# crystal-oscillators.net
KiCad netlist of a schematic drawn in EAGLE
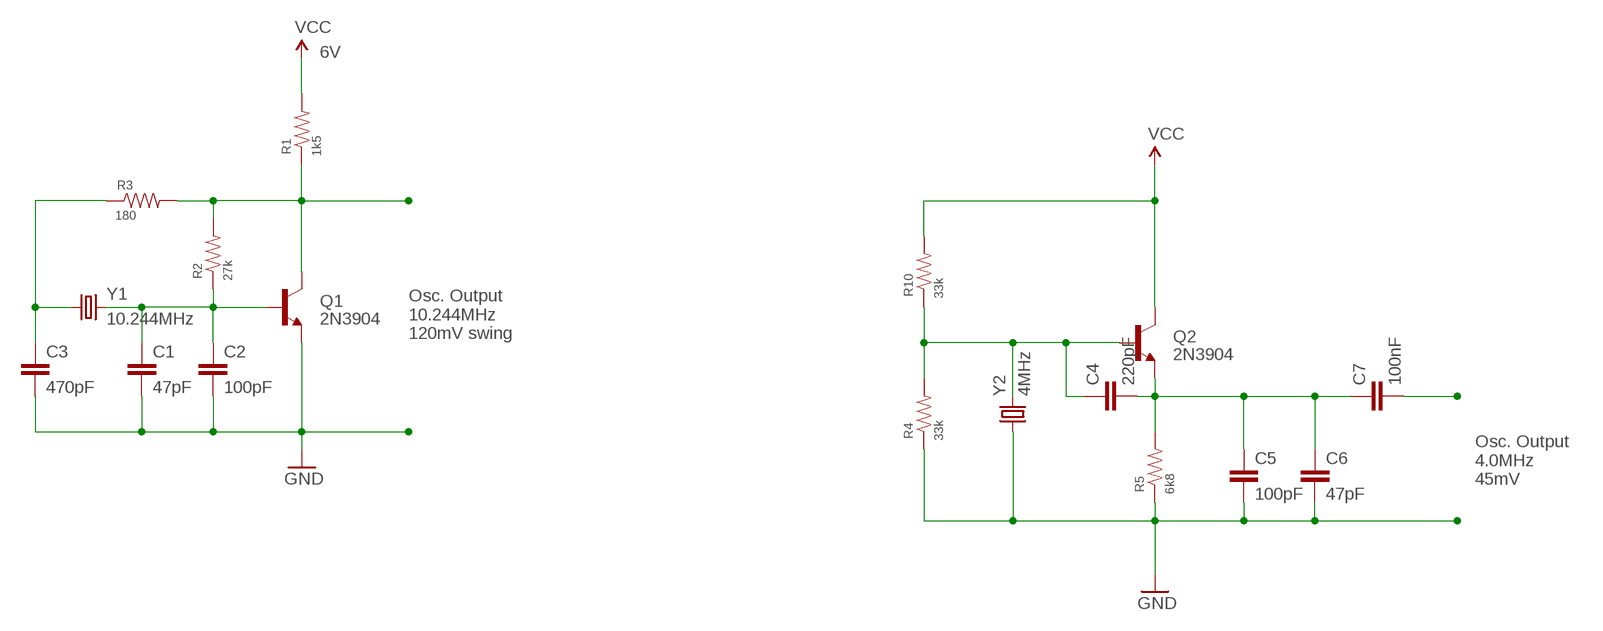
[diagram p0: schematic, sheet 1]

(export (version "E")
  (design (tool "Eeschema 10.0.6"))
  (components
    (comp (ref "C1")
      (value "47pF")
      (footprint "eagle-import:CAP-PTH-SMALL")
      (libsource (lib "eagle-import") (part "CAPPTH"))
    )
    (comp (ref "C2")
      (value "100pF")
      (footprint "eagle-import:CAP-PTH-SMALL")
      (libsource (lib "eagle-import") (part "CAPPTH"))
    )
    (comp (ref "C3")
      (value "470pF")
      (footprint "eagle-import:CAP-PTH-SMALL")
      (libsource (lib "eagle-import") (part "CAPPTH"))
    )
    (comp (ref "C4")
      (value "220pF")
      (footprint "eagle-import:CAP-PTH-SMALL")
      (libsource (lib "eagle-import") (part "CAPPTH"))
    )
    (comp (ref "C5")
      (value "100pF")
      (footprint "eagle-import:CAP-PTH-SMALL")
      (libsource (lib "eagle-import") (part "CAPPTH"))
    )
    (comp (ref "C6")
      (value "47pF")
      (footprint "eagle-import:CAP-PTH-SMALL")
      (libsource (lib "eagle-import") (part "CAPPTH"))
    )
    (comp (ref "C7")
      (value "100nF")
      (footprint "eagle-import:CAP-PTH-SMALL")
      (libsource (lib "eagle-import") (part "CAPPTH"))
    )
    (comp (ref "Q1")
      (value "2N3904")
      (footprint "eagle-import:TO-92")
      (libsource (lib "eagle-import") (part "TRANSISTOR_NPNP2N2222A"))
    )
    (comp (ref "Q2")
      (value "2N3904")
      (footprint "eagle-import:TO-92")
      (libsource (lib "eagle-import") (part "TRANSISTOR_NPNP2N2222A"))
    )
    (comp (ref "R1")
      (value "1k5")
      (footprint "eagle-import:VERT-PTH")
      (libsource (lib "eagle-import") (part "RESISTOR-PTH"))
    )
    (comp (ref "R2")
      (value "27k")
      (footprint "eagle-import:VERT-PTH")
      (libsource (lib "eagle-import") (part "RESISTOR-PTH"))
    )
    (comp (ref "R3")
      (value "180")
      (footprint "eagle-import:VERT-PTH")
      (libsource (lib "eagle-import") (part "RESISTOR-PTH"))
    )
    (comp (ref "R4")
      (value "33k")
      (footprint "eagle-import:VERT-PTH")
      (libsource (lib "eagle-import") (part "RESISTOR-PTH"))
    )
    (comp (ref "R5")
      (value "6k8")
      (footprint "eagle-import:VERT-PTH")
      (libsource (lib "eagle-import") (part "RESISTOR-PTH"))
    )
    (comp (ref "R10")
      (value "33k")
      (footprint "eagle-import:VERT-PTH")
      (libsource (lib "eagle-import") (part "RESISTOR-PTH"))
    )
    (comp (ref "Y1")
      (value "10.244MHz")
      (footprint "eagle-import:HC49US")
      (libsource (lib "eagle-import") (part "CRYSTALHC49US"))
    )
    (comp (ref "Y2")
      (value "4MHz")
      (footprint "eagle-import:HC49US")
      (libsource (lib "eagle-import") (part "CRYSTALHC49US"))
    )
  )
  (nets
    (net (code "1") (name "GND") (class "Default")
      (node (ref "C1") (pin "2") (pinfunction "2_2") (pintype "passive"))
      (node (ref "C2") (pin "2") (pinfunction "2_2") (pintype "passive"))
      (node (ref "C3") (pin "2") (pinfunction "2_2") (pintype "passive"))
      (node (ref "C5") (pin "2") (pinfunction "2_2") (pintype "passive"))
      (node (ref "C6") (pin "2") (pinfunction "2_2") (pintype "passive"))
      (node (ref "Q1") (pin "3") (pinfunction "E_3") (pintype "passive"))
      (node (ref "R4") (pin "1") (pinfunction "G$1_1") (pintype "bidirectional"))
      (node (ref "R5") (pin "1") (pinfunction "G$1_1") (pintype "bidirectional"))
      (node (ref "Y2") (pin "1") (pinfunction "1_1") (pintype "passive"))
    )
    (net (code "2") (name "Net-(Q1-B)") (class "Default")
      (node (ref "C1") (pin "1") (pinfunction "1_1") (pintype "passive"))
      (node (ref "C2") (pin "1") (pinfunction "1_1") (pintype "passive"))
      (node (ref "Q1") (pin "2") (pinfunction "B_2") (pintype "passive"))
      (node (ref "R2") (pin "1") (pinfunction "G$1_1") (pintype "bidirectional"))
      (node (ref "Y1") (pin "2") (pinfunction "2_2") (pintype "passive"))
    )
    (net (code "3") (name "Net-(Q1-C)") (class "Default")
      (node (ref "Q1") (pin "1") (pinfunction "C_1") (pintype "passive"))
      (node (ref "R1") (pin "1") (pinfunction "G$1_1") (pintype "bidirectional"))
      (node (ref "R2") (pin "2") (pinfunction "G$2_2") (pintype "bidirectional"))
      (node (ref "R3") (pin "2") (pinfunction "G$2_2") (pintype "bidirectional"))
    )
    (net (code "4") (name "Net-(Q2-B)") (class "Default")
      (node (ref "C4") (pin "1") (pinfunction "1_1") (pintype "passive"))
      (node (ref "Q2") (pin "2") (pinfunction "B_2") (pintype "passive"))
      (node (ref "R10") (pin "1") (pinfunction "G$1_1") (pintype "bidirectional"))
      (node (ref "R4") (pin "2") (pinfunction "G$2_2") (pintype "bidirectional"))
      (node (ref "Y2") (pin "2") (pinfunction "2_2") (pintype "passive"))
    )
    (net (code "5") (name "Net-(Q2-E)") (class "Default")
      (node (ref "C4") (pin "2") (pinfunction "2_2") (pintype "passive"))
      (node (ref "C5") (pin "1") (pinfunction "1_1") (pintype "passive"))
      (node (ref "C6") (pin "1") (pinfunction "1_1") (pintype "passive"))
      (node (ref "C7") (pin "1") (pinfunction "1_1") (pintype "passive"))
      (node (ref "Q2") (pin "3") (pinfunction "E_3") (pintype "passive"))
      (node (ref "R5") (pin "2") (pinfunction "G$2_2") (pintype "bidirectional"))
    )
    (net (code "6") (name "Net-(R3-G$1)") (class "Default")
      (node (ref "C3") (pin "1") (pinfunction "1_1") (pintype "passive"))
      (node (ref "R3") (pin "1") (pinfunction "G$1_1") (pintype "bidirectional"))
      (node (ref "Y1") (pin "1") (pinfunction "1_1") (pintype "passive"))
    )
    (net (code "7") (name "VCC") (class "Default")
      (node (ref "Q2") (pin "1") (pinfunction "C_1") (pintype "passive"))
      (node (ref "R1") (pin "2") (pinfunction "G$2_2") (pintype "bidirectional"))
      (node (ref "R10") (pin "2") (pinfunction "G$2_2") (pintype "bidirectional"))
    )
    (net (code "8") (name "unconnected-(C7-Pad2)") (class "Default")
      (node (ref "C7") (pin "2") (pinfunction "2_2") (pintype "passive"))
    )
  )
)
